# Sheet1_4.net
KiCad netlist of a schematic drawn in Altium Designer
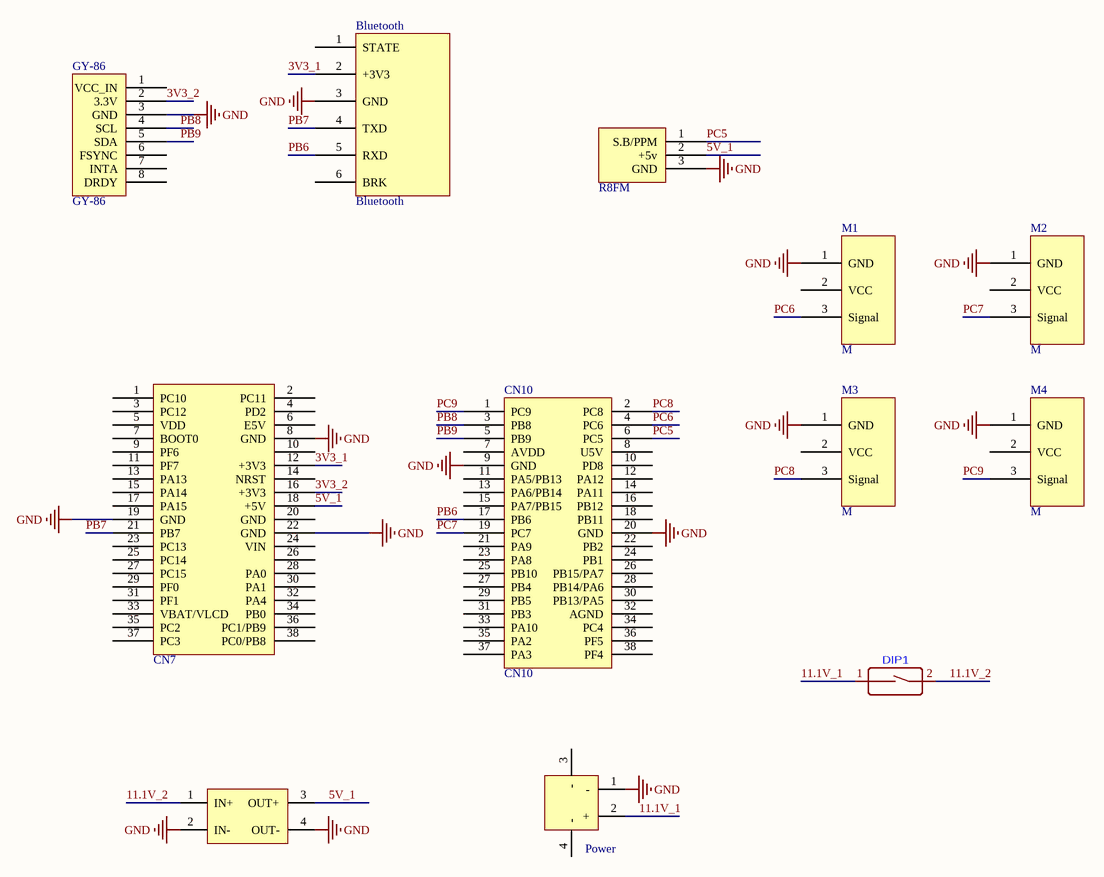
[diagram p0: Sheet1 (4).SchDoc]

(export (version "E")
  (design (tool "Eeschema 10.0.6"))
  (components
    (comp (ref "Bluetooth")
      (value "Bluetooth")
      (footprint "bluetooth")
      (libsource (lib "Integrated_Library") (part "Bluetooth"))
    )
    (comp (ref "CN7")
      (value "CN7")
      (footprint "Header 19X2")
      (libsource (lib "Integrated_Library") (part "CN7"))
    )
    (comp (ref "CN10")
      (value "CN10")
      (footprint "Header 19X2")
      (libsource (lib "Integrated_Library") (part "CN10"))
    )
    (comp (ref "DIP1")
      (value "~")
      (footprint "SW")
      (libsource (lib "altium-import") (part "root_0_拨码开关 2.54*1_"))
    )
    (comp (ref "GY-86") (value "GY-86") (footprint "GY-86") (libsource (lib "Schlib1") (part "GY-86")))
    (comp (ref "M1") (value "M") (footprint "Motor") (libsource (lib "Integrated_Library") (part "M")))
    (comp (ref "M2") (value "M") (footprint "Motor") (libsource (lib "Integrated_Library") (part "M")))
    (comp (ref "M3") (value "M") (footprint "Motor") (libsource (lib "Integrated_Library") (part "M")))
    (comp (ref "M4") (value "M") (footprint "Motor") (libsource (lib "Integrated_Library") (part "M")))
    (comp (ref "Power") (value "Power") (footprint "Power") (libsource (lib "Schlib1") (part "Power")))
    (comp (ref "R8FM") (value "R8FM") (footprint "R8FM") (libsource (lib "Schlib1") (part "R8FM")))
    (comp (ref "Voltage") (value "*") (footprint "DM02") (libsource (lib "*") (part "Component_1")))
  )
  (nets
    (net (code "1") (name "/3V3_1") (class "Default")
      (node (ref "Bluetooth") (pin "2") (pinfunction "+3V3_2") (pintype "passive"))
      (node (ref "CN7") (pin "12") (pinfunction "+3V3_12") (pintype "passive"))
    )
    (net (code "2") (name "/3V3_2") (class "Default")
      (node (ref "CN7") (pin "16") (pinfunction "+3V3_16") (pintype "passive"))
      (node (ref "GY-86") (pin "2") (pinfunction "3.3V_2") (pintype "passive"))
    )
    (net (code "3") (name "/5V_1") (class "Default")
      (node (ref "CN7") (pin "18") (pinfunction "+5V_18") (pintype "passive"))
      (node (ref "R8FM") (pin "2") (pinfunction "+5v_2") (pintype "passive"))
      (node (ref "Voltage") (pin "3") (pinfunction "OUT+_3") (pintype "passive"))
    )
    (net (code "4") (name "/11.1V_1") (class "Default")
      (node (ref "DIP1") (pin "1") (pinfunction "1_1") (pintype "passive"))
      (node (ref "Power") (pin "2") (pinfunction "+_2") (pintype "passive"))
    )
    (net (code "5") (name "/11.1V_2") (class "Default")
      (node (ref "DIP1") (pin "2") (pinfunction "2_2") (pintype "passive"))
      (node (ref "Voltage") (pin "1") (pinfunction "IN+_1") (pintype "passive"))
    )
    (net (code "7") (name "/PB6") (class "Default")
      (node (ref "Bluetooth") (pin "5") (pinfunction "RXD_5") (pintype "passive"))
      (node (ref "CN10") (pin "17") (pinfunction "PB6_17") (pintype "passive"))
    )
    (net (code "8") (name "/PB7") (class "Default")
      (node (ref "Bluetooth") (pin "4") (pinfunction "TXD_4") (pintype "passive"))
      (node (ref "CN7") (pin "21") (pinfunction "PB7_21") (pintype "passive"))
    )
    (net (code "9") (name "/PB8") (class "Default")
      (node (ref "CN10") (pin "3") (pinfunction "PB8_3") (pintype "passive"))
      (node (ref "GY-86") (pin "4") (pinfunction "SCL_4") (pintype "passive"))
    )
    (net (code "10") (name "/PB9") (class "Default")
      (node (ref "CN10") (pin "5") (pinfunction "PB9_5") (pintype "passive"))
      (node (ref "GY-86") (pin "5") (pinfunction "SDA_5") (pintype "passive"))
    )
    (net (code "11") (name "/PC5") (class "Default")
      (node (ref "CN10") (pin "6") (pinfunction "PC5_6") (pintype "passive"))
      (node (ref "R8FM") (pin "1") (pinfunction "S.B/PPM_1") (pintype "passive"))
    )
    (net (code "12") (name "/PC6") (class "Default")
      (node (ref "CN10") (pin "4") (pinfunction "PC6_4") (pintype "passive"))
      (node (ref "M1") (pin "3") (pinfunction "Signal_3") (pintype "passive"))
    )
    (net (code "13") (name "/PC7") (class "Default")
      (node (ref "CN10") (pin "19") (pinfunction "PC7_19") (pintype "passive"))
      (node (ref "M2") (pin "3") (pinfunction "Signal_3") (pintype "passive"))
    )
    (net (code "14") (name "/PC8") (class "Default")
      (node (ref "CN10") (pin "2") (pinfunction "PC8_2") (pintype "passive"))
      (node (ref "M3") (pin "3") (pinfunction "Signal_3") (pintype "passive"))
    )
    (net (code "15") (name "/PC9") (class "Default")
      (node (ref "CN10") (pin "1") (pinfunction "PC9_1") (pintype "passive"))
      (node (ref "M4") (pin "3") (pinfunction "Signal_3") (pintype "passive"))
    )
    (net (code "16") (name "GND") (class "Default")
      (node (ref "Bluetooth") (pin "3") (pinfunction "GND_3") (pintype "passive"))
      (node (ref "CN10") (pin "20") (pinfunction "GND_20") (pintype "passive"))
      (node (ref "CN10") (pin "9") (pinfunction "GND_9") (pintype "passive"))
      (node (ref "CN7") (pin "19") (pinfunction "GND_19") (pintype "passive"))
      (node (ref "CN7") (pin "22") (pinfunction "GND_22") (pintype "passive"))
      (node (ref "CN7") (pin "8") (pinfunction "GND_8") (pintype "passive"))
      (node (ref "GY-86") (pin "3") (pinfunction "GND_3") (pintype "passive"))
      (node (ref "M1") (pin "1") (pinfunction "GND_1") (pintype "passive"))
      (node (ref "M2") (pin "1") (pinfunction "GND_1") (pintype "passive"))
      (node (ref "M3") (pin "1") (pinfunction "GND_1") (pintype "passive"))
      (node (ref "M4") (pin "1") (pinfunction "GND_1") (pintype "passive"))
      (node (ref "Power") (pin "1") (pinfunction "-_1") (pintype "passive"))
      (node (ref "R8FM") (pin "3") (pinfunction "GND_3") (pintype "passive"))
      (node (ref "Voltage") (pin "2") (pinfunction "IN-_2") (pintype "passive"))
      (node (ref "Voltage") (pin "4") (pinfunction "OUT-_4") (pintype "passive"))
    )
    (net (code "17") (name "unconnected-(Bluetooth-BRK-Pad6)") (class "Default")
      (node (ref "Bluetooth") (pin "6") (pinfunction "BRK_6") (pintype "passive"))
    )
    (net (code "18") (name "unconnected-(Bluetooth-STATE-Pad1)") (class "Default")
      (node (ref "Bluetooth") (pin "1") (pinfunction "STATE_1") (pintype "passive"))
    )
    (net (code "19") (name "unconnected-(CN7-BOOT0-Pad7)") (class "Default")
      (node (ref "CN7") (pin "7") (pinfunction "BOOT0_7") (pintype "passive"))
    )
    (net (code "20") (name "unconnected-(CN7-E5V-Pad6)") (class "Default")
      (node (ref "CN7") (pin "6") (pinfunction "E5V_6") (pintype "passive"))
    )
    (net (code "21") (name "unconnected-(CN7-GND-Pad20)") (class "Default")
      (node (ref "CN7") (pin "20") (pinfunction "GND_20") (pintype "passive"))
    )
    (net (code "22") (name "unconnected-(CN7-NRST-Pad14)") (class "Default")
      (node (ref "CN7") (pin "14") (pinfunction "NRST_14") (pintype "passive"))
    )
    (net (code "23") (name "unconnected-(CN7-PA0-Pad28)") (class "Default")
      (node (ref "CN7") (pin "28") (pinfunction "PA0_28") (pintype "passive"))
    )
    (net (code "24") (name "unconnected-(CN7-PA1-Pad30)") (class "Default")
      (node (ref "CN7") (pin "30") (pinfunction "PA1_30") (pintype "passive"))
    )
    (net (code "25") (name "unconnected-(CN7-PA4-Pad32)") (class "Default")
      (node (ref "CN7") (pin "32") (pinfunction "PA4_32") (pintype "passive"))
    )
    (net (code "26") (name "unconnected-(CN7-PA13-Pad13)") (class "Default")
      (node (ref "CN7") (pin "13") (pinfunction "PA13_13") (pintype "passive"))
    )
    (net (code "27") (name "unconnected-(CN7-PA14-Pad15)") (class "Default")
      (node (ref "CN7") (pin "15") (pinfunction "PA14_15") (pintype "passive"))
    )
    (net (code "28") (name "unconnected-(CN7-PA15-Pad17)") (class "Default")
      (node (ref "CN7") (pin "17") (pinfunction "PA15_17") (pintype "passive"))
    )
    (net (code "29") (name "unconnected-(CN7-PB0-Pad34)") (class "Default")
      (node (ref "CN7") (pin "34") (pinfunction "PB0_34") (pintype "passive"))
    )
    (net (code "30") (name "unconnected-(CN7-PC0{slash}PB8-Pad38)") (class "Default")
      (node (ref "CN7") (pin "38") (pinfunction "PC0/PB8_38") (pintype "passive"))
    )
    (net (code "31") (name "unconnected-(CN7-PC1{slash}PB9-Pad36)") (class "Default")
      (node (ref "CN7") (pin "36") (pinfunction "PC1/PB9_36") (pintype "passive"))
    )
    (net (code "32") (name "unconnected-(CN7-PC2-Pad35)") (class "Default")
      (node (ref "CN7") (pin "35") (pinfunction "PC2_35") (pintype "passive"))
    )
    (net (code "33") (name "unconnected-(CN7-PC3-Pad37)") (class "Default")
      (node (ref "CN7") (pin "37") (pinfunction "PC3_37") (pintype "passive"))
    )
    (net (code "34") (name "unconnected-(CN7-PC10-Pad1)") (class "Default")
      (node (ref "CN7") (pin "1") (pinfunction "PC10_1") (pintype "passive"))
    )
    (net (code "35") (name "unconnected-(CN7-PC11-Pad2)") (class "Default")
      (node (ref "CN7") (pin "2") (pinfunction "PC11_2") (pintype "passive"))
    )
    (net (code "36") (name "unconnected-(CN7-PC12-Pad3)") (class "Default")
      (node (ref "CN7") (pin "3") (pinfunction "PC12_3") (pintype "passive"))
    )
    (net (code "37") (name "unconnected-(CN7-PC13-Pad23)") (class "Default")
      (node (ref "CN7") (pin "23") (pinfunction "PC13_23") (pintype "passive"))
    )
    (net (code "38") (name "unconnected-(CN7-PC14-Pad25)") (class "Default")
      (node (ref "CN7") (pin "25") (pinfunction "PC14_25") (pintype "passive"))
    )
    (net (code "39") (name "unconnected-(CN7-PC15-Pad27)") (class "Default")
      (node (ref "CN7") (pin "27") (pinfunction "PC15_27") (pintype "passive"))
    )
    (net (code "40") (name "unconnected-(CN7-PD2-Pad4)") (class "Default")
      (node (ref "CN7") (pin "4") (pinfunction "PD2_4") (pintype "passive"))
    )
    (net (code "41") (name "unconnected-(CN7-PF0-Pad29)") (class "Default")
      (node (ref "CN7") (pin "29") (pinfunction "PF0_29") (pintype "passive"))
    )
    (net (code "42") (name "unconnected-(CN7-PF1-Pad31)") (class "Default")
      (node (ref "CN7") (pin "31") (pinfunction "PF1_31") (pintype "passive"))
    )
    (net (code "43") (name "unconnected-(CN7-PF6-Pad9)") (class "Default")
      (node (ref "CN7") (pin "9") (pinfunction "PF6_9") (pintype "passive"))
    )
    (net (code "44") (name "unconnected-(CN7-PF7-Pad11)") (class "Default")
      (node (ref "CN7") (pin "11") (pinfunction "PF7_11") (pintype "passive"))
    )
    (net (code "45") (name "unconnected-(CN7-Pad10)") (class "Default")
      (node (ref "CN7") (pin "10") (pintype "passive"))
    )
    (net (code "46") (name "unconnected-(CN7-Pad26)") (class "Default")
      (node (ref "CN7") (pin "26") (pintype "passive"))
    )
    (net (code "47") (name "unconnected-(CN7-VBAT{slash}VLCD-Pad33)") (class "Default")
      (node (ref "CN7") (pin "33") (pinfunction "VBAT/VLCD_33") (pintype "passive"))
    )
    (net (code "48") (name "unconnected-(CN7-VDD-Pad5)") (class "Default")
      (node (ref "CN7") (pin "5") (pinfunction "VDD_5") (pintype "passive"))
    )
    (net (code "49") (name "unconnected-(CN7-VIN-Pad24)") (class "Default")
      (node (ref "CN7") (pin "24") (pinfunction "VIN_24") (pintype "passive"))
    )
    (net (code "50") (name "unconnected-(CN10-AGND-Pad32)") (class "Default")
      (node (ref "CN10") (pin "32") (pinfunction "AGND_32") (pintype "passive"))
    )
    (net (code "51") (name "unconnected-(CN10-AVDD-Pad7)") (class "Default")
      (node (ref "CN10") (pin "7") (pinfunction "AVDD_7") (pintype "passive"))
    )
    (net (code "52") (name "unconnected-(CN10-PA2-Pad35)") (class "Default")
      (node (ref "CN10") (pin "35") (pinfunction "PA2_35") (pintype "passive"))
    )
    (net (code "53") (name "unconnected-(CN10-PA3-Pad37)") (class "Default")
      (node (ref "CN10") (pin "37") (pinfunction "PA3_37") (pintype "passive"))
    )
    (net (code "54") (name "unconnected-(CN10-PA5{slash}PB13-Pad11)") (class "Default")
      (node (ref "CN10") (pin "11") (pinfunction "PA5/PB13_11") (pintype "passive"))
    )
    (net (code "55") (name "unconnected-(CN10-PA6{slash}PB14-Pad13)") (class "Default")
      (node (ref "CN10") (pin "13") (pinfunction "PA6/PB14_13") (pintype "passive"))
    )
    (net (code "56") (name "unconnected-(CN10-PA7{slash}PB15-Pad15)") (class "Default")
      (node (ref "CN10") (pin "15") (pinfunction "PA7/PB15_15") (pintype "passive"))
    )
    (net (code "57") (name "unconnected-(CN10-PA8-Pad23)") (class "Default")
      (node (ref "CN10") (pin "23") (pinfunction "PA8_23") (pintype "passive"))
    )
    (net (code "58") (name "unconnected-(CN10-PA9-Pad21)") (class "Default")
      (node (ref "CN10") (pin "21") (pinfunction "PA9_21") (pintype "passive"))
    )
    (net (code "59") (name "unconnected-(CN10-PA10-Pad33)") (class "Default")
      (node (ref "CN10") (pin "33") (pinfunction "PA10_33") (pintype "passive"))
    )
    (net (code "60") (name "unconnected-(CN10-PA11-Pad14)") (class "Default")
      (node (ref "CN10") (pin "14") (pinfunction "PA11_14") (pintype "passive"))
    )
    (net (code "61") (name "unconnected-(CN10-PA12-Pad12)") (class "Default")
      (node (ref "CN10") (pin "12") (pinfunction "PA12_12") (pintype "passive"))
    )
    (net (code "62") (name "unconnected-(CN10-PB1-Pad24)") (class "Default")
      (node (ref "CN10") (pin "24") (pinfunction "PB1_24") (pintype "passive"))
    )
    (net (code "63") (name "unconnected-(CN10-PB2-Pad22)") (class "Default")
      (node (ref "CN10") (pin "22") (pinfunction "PB2_22") (pintype "passive"))
    )
    (net (code "64") (name "unconnected-(CN10-PB3-Pad31)") (class "Default")
      (node (ref "CN10") (pin "31") (pinfunction "PB3_31") (pintype "passive"))
    )
    (net (code "65") (name "unconnected-(CN10-PB4-Pad27)") (class "Default")
      (node (ref "CN10") (pin "27") (pinfunction "PB4_27") (pintype "passive"))
    )
    (net (code "66") (name "unconnected-(CN10-PB5-Pad29)") (class "Default")
      (node (ref "CN10") (pin "29") (pinfunction "PB5_29") (pintype "passive"))
    )
    (net (code "67") (name "unconnected-(CN10-PB10-Pad25)") (class "Default")
      (node (ref "CN10") (pin "25") (pinfunction "PB10_25") (pintype "passive"))
    )
    (net (code "68") (name "unconnected-(CN10-PB11-Pad18)") (class "Default")
      (node (ref "CN10") (pin "18") (pinfunction "PB11_18") (pintype "passive"))
    )
    (net (code "69") (name "unconnected-(CN10-PB12-Pad16)") (class "Default")
      (node (ref "CN10") (pin "16") (pinfunction "PB12_16") (pintype "passive"))
    )
    (net (code "70") (name "unconnected-(CN10-PB13{slash}PA5-Pad30)") (class "Default")
      (node (ref "CN10") (pin "30") (pinfunction "PB13/PA5_30") (pintype "passive"))
    )
    (net (code "71") (name "unconnected-(CN10-PB14{slash}PA6-Pad28)") (class "Default")
      (node (ref "CN10") (pin "28") (pinfunction "PB14/PA6_28") (pintype "passive"))
    )
    (net (code "72") (name "unconnected-(CN10-PB15{slash}PA7-Pad26)") (class "Default")
      (node (ref "CN10") (pin "26") (pinfunction "PB15/PA7_26") (pintype "passive"))
    )
    (net (code "73") (name "unconnected-(CN10-PC4-Pad34)") (class "Default")
      (node (ref "CN10") (pin "34") (pinfunction "PC4_34") (pintype "passive"))
    )
    (net (code "74") (name "unconnected-(CN10-PD8-Pad10)") (class "Default")
      (node (ref "CN10") (pin "10") (pinfunction "PD8_10") (pintype "passive"))
    )
    (net (code "75") (name "unconnected-(CN10-PF4-Pad38)") (class "Default")
      (node (ref "CN10") (pin "38") (pinfunction "PF4_38") (pintype "passive"))
    )
    (net (code "76") (name "unconnected-(CN10-PF5-Pad36)") (class "Default")
      (node (ref "CN10") (pin "36") (pinfunction "PF5_36") (pintype "passive"))
    )
    (net (code "77") (name "unconnected-(CN10-U5V-Pad8)") (class "Default")
      (node (ref "CN10") (pin "8") (pinfunction "U5V_8") (pintype "passive"))
    )
    (net (code "78") (name "unconnected-(GY-86-DRDY-Pad8)") (class "Default")
      (node (ref "GY-86") (pin "8") (pinfunction "DRDY_8") (pintype "passive"))
    )
    (net (code "79") (name "unconnected-(GY-86-FSYNC-Pad6)") (class "Default")
      (node (ref "GY-86") (pin "6") (pinfunction "FSYNC_6") (pintype "passive"))
    )
    (net (code "80") (name "unconnected-(GY-86-INTA-Pad7)") (class "Default")
      (node (ref "GY-86") (pin "7") (pinfunction "INTA_7") (pintype "passive"))
    )
    (net (code "81") (name "unconnected-(GY-86-VCC_IN-Pad1)") (class "Default")
      (node (ref "GY-86") (pin "1") (pinfunction "VCC_IN_1") (pintype "passive"))
    )
    (net (code "82") (name "unconnected-(M1-VCC-Pad2)") (class "Default")
      (node (ref "M1") (pin "2") (pinfunction "VCC_2") (pintype "passive"))
    )
    (net (code "83") (name "unconnected-(M2-VCC-Pad2)") (class "Default")
      (node (ref "M2") (pin "2") (pinfunction "VCC_2") (pintype "passive"))
    )
    (net (code "84") (name "unconnected-(M3-VCC-Pad2)") (class "Default")
      (node (ref "M3") (pin "2") (pinfunction "VCC_2") (pintype "passive"))
    )
    (net (code "85") (name "unconnected-(M4-VCC-Pad2)") (class "Default")
      (node (ref "M4") (pin "2") (pinfunction "VCC_2") (pintype "passive"))
    )
    (net (code "86") (name "unconnected-(Power---Pad3)") (class "Default")
      (node (ref "Power") (pin "3") (pinfunction "-_3") (pintype "passive"))
    )
    (net (code "87") (name "unconnected-(Power---Pad4)") (class "Default")
      (node (ref "Power") (pin "4") (pinfunction "-_4") (pintype "passive"))
    )
  )
)
